# schematic.net
KiCad netlist of a schematic drawn in Altium Designer
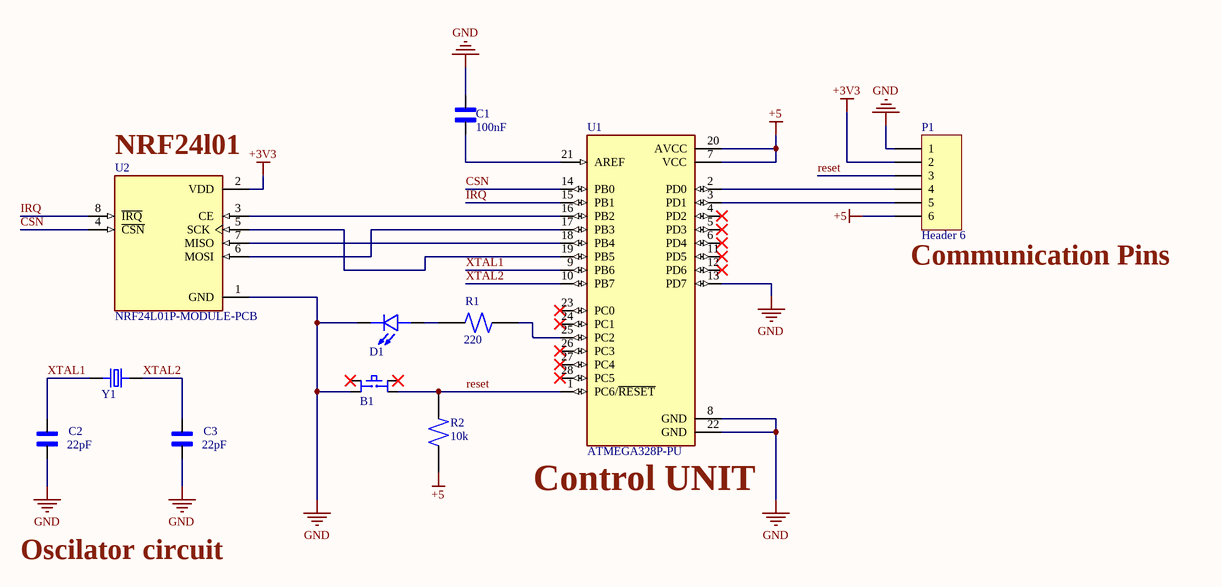
[diagram p0: schematic.SchDoc]

(export (version "E")
  (design (tool "Eeschema 10.0.6"))
  (components
    (comp (ref "B1")
      (value "Push button")
      (footprint "SW_TS02-66-95-BK-260-LCR-D")
      (libsource (lib "Installed library") (part "Push button"))
    )
    (comp (ref "C1")
      (value "100nF")
      (footprint "CAPRB500W50L450T300H550")
      (description "2200 pF Â±10% 250V Ceramic Capacitor X7R Radial")
      (fields (field (name "DIGI-KEY_PART_NUMBER") "445-173386-1-ND") (field (name "MF") "TDK"))
      (libsource (lib "Installed library") (part "Ceramic capacitor"))
    )
    (comp (ref "C2")
      (value "22pF")
      (footprint "CAPRB500W50L450T300H550")
      (description "2200 pF Â±10% 250V Ceramic Capacitor X7R Radial")
      (fields (field (name "DIGI-KEY_PART_NUMBER") "445-173386-1-ND") (field (name "MF") "TDK"))
      (libsource (lib "") (part "Ceramic capacitor_1"))
    )
    (comp (ref "C3")
      (value "22pF")
      (footprint "CAPRB500W50L450T300H550")
      (description "2200 pF Â±10% 250V Ceramic Capacitor X7R Radial")
      (fields (field (name "DIGI-KEY_PART_NUMBER") "445-173386-1-ND") (field (name "MF") "TDK"))
      (libsource (lib "") (part "Ceramic capacitor_1"))
    )
    (comp (ref "D1")
      (value "L08R5000Q1")
      (footprint "LEDRD254W57D500H1070")
      (description "LED, Orange, Through Hole, T-1 3/4 (5mm), 30 mA, 2.1 V, 635 nm")
      (fields (field (name "MF") "{'manufacturer': u'LED Technology'}"))
      (libsource (lib "Installed library") (part "LED"))
    )
    (comp (ref "P1")
      (value "Header 6")
      (footprint "HDR1X6")
      (description "Header, 6-Pin")
      (fields (field (name "PUBLISHER") "Altium Limited"))
      (libsource (lib "Miscellaneous Connectors") (part "Header 6"))
    )
    (comp (ref "R1")
      (value "220")
      (footprint "RESAD1100W55L680D260")
      (description "(MFR-25FBF52-10K) 10,2 kOhm bei 1% 0,25W, 1/4W Durchbohrlochwiderstand Axial Metal Film")
      (fields (field (name "DIGI-KEY_PART_NUMBER") "10.2KXBK-ND") (field (name "MF") "Yageo"))
      (libsource (lib "Installed library") (part "Resistor (0.25W)"))
    )
    (comp (ref "R2")
      (value "10k")
      (footprint "RESAD1100W55L680D260")
      (description "(MFR-25FBF52-10K) 10,2 kOhm bei 1% 0,25W, 1/4W Durchbohrlochwiderstand Axial Metal Film")
      (fields (field (name "DIGI-KEY_PART_NUMBER") "10.2KXBK-ND") (field (name "MF") "Yageo"))
      (libsource (lib "Installed library") (part "Resistor (0.25W)"))
    )
    (comp (ref "U1")
      (value "ATMEGA328P-PU")
      (footprint "DIP794W46P254L2967H457Q28B")
      (description "ATmega Series 20 MHz 32 KB Flash 2 KB SRAM 8-Bit Microcontroller - DIP-28")
      (libsource (lib "Installed library") (part "ATMEGA328P-PU"))
    )
    (comp (ref "U2")
      (value "NRF24L01P-MODULE-PCB")
      (footprint "XCVR_NRF24L01P-MODULE-PCB")
      (description "- Transceiver For Use With nRF24L01+")
      (fields (field (name "MF") "Nordic Semiconductor"))
      (libsource (lib "NRF24L01P-MODULE-PCB") (part "NRF24L01P-MODULE-PCB"))
    )
    (comp (ref "Y1")
      (value "ECS-160-S-4")
      (footprint "XTAL_ECS-160-20-4X")
      (description "CRYSTAL T/H")
      (fields (field (name "MF") "{'manufacturer': u'ECS Inc.'}"))
      (libsource (lib "Installed library") (part "Crystal oscilator"))
    )
  )
  (nets
    (net (code "1") (name "+3V3") (class "Default")
      (node (ref "P1") (pin "2") (pinfunction "2_2") (pintype "passive"))
      (node (ref "U2") (pin "2") (pinfunction "VDD_2") (pintype "power_in"))
    )
    (net (code "2") (name "+5") (class "Default")
      (node (ref "P1") (pin "6") (pinfunction "6_6") (pintype "passive"))
      (node (ref "R2") (pin "1") (pinfunction "1_1") (pintype "passive"))
      (node (ref "U1") (pin "20") (pinfunction "AVCC_20") (pintype "power_in"))
      (node (ref "U1") (pin "7") (pinfunction "VCC_7") (pintype "power_in"))
    )
    (net (code "3") (name "/CSN") (class "Default")
      (node (ref "U1") (pin "14") (pinfunction "PB0_14") (pintype "bidirectional"))
      (node (ref "U2") (pin "4") (pinfunction "~{CSN}_4") (pintype "input"))
    )
    (net (code "4") (name "/IRQ") (class "Default")
      (node (ref "U1") (pin "15") (pinfunction "PB1_15") (pintype "bidirectional"))
      (node (ref "U2") (pin "8") (pinfunction "~{IRQ}_8") (pintype "input"))
    )
    (net (code "5") (name "/XTAL1") (class "Default")
      (node (ref "C2") (pin "2") (pinfunction "2_2") (pintype "passive"))
      (node (ref "U1") (pin "9") (pinfunction "PB6_9") (pintype "bidirectional"))
      (node (ref "Y1") (pin "1") (pinfunction "1_1") (pintype "passive"))
    )
    (net (code "6") (name "/XTAL2") (class "Default")
      (node (ref "C3") (pin "2") (pinfunction "2_2") (pintype "passive"))
      (node (ref "U1") (pin "10") (pinfunction "PB7_10") (pintype "bidirectional"))
      (node (ref "Y1") (pin "2") (pinfunction "2_2") (pintype "passive"))
    )
    (net (code "7") (name "/reset") (class "Default")
      (node (ref "B1") (pin "4") (pinfunction "4_4") (pintype "passive"))
      (node (ref "P1") (pin "3") (pinfunction "3_3") (pintype "passive"))
      (node (ref "R2") (pin "2") (pinfunction "2_2") (pintype "passive"))
      (node (ref "U1") (pin "1") (pinfunction "PC6/~{RESET}_1") (pintype "bidirectional"))
    )
    (net (code "8") (name "GND") (class "Default")
      (node (ref "B1") (pin "2") (pinfunction "2_2") (pintype "passive"))
      (node (ref "C1") (pin "1") (pinfunction "1_1") (pintype "passive"))
      (node (ref "C2") (pin "1") (pinfunction "1_1") (pintype "passive"))
      (node (ref "C3") (pin "1") (pinfunction "1_1") (pintype "passive"))
      (node (ref "D1") (pin "C") (pinfunction "C_C") (pintype "passive"))
      (node (ref "P1") (pin "1") (pinfunction "1_1") (pintype "passive"))
      (node (ref "U1") (pin "13") (pinfunction "PD7_13") (pintype "bidirectional"))
      (node (ref "U1") (pin "22") (pinfunction "GND_22") (pintype "power_in"))
      (node (ref "U1") (pin "8") (pinfunction "GND_8") (pintype "power_in"))
      (node (ref "U2") (pin "1") (pinfunction "GND_1") (pintype "power_in"))
    )
    (net (code "9") (name "Net-(D1-PadA)") (class "Default")
      (node (ref "D1") (pin "A") (pinfunction "A_A") (pintype "passive"))
      (node (ref "R1") (pin "2") (pinfunction "2_2") (pintype "passive"))
    )
    (net (code "10") (name "Net-(U1-AREF)") (class "Default")
      (node (ref "C1") (pin "2") (pinfunction "2_2") (pintype "passive"))
      (node (ref "U1") (pin "21") (pinfunction "AREF_21") (pintype "input"))
    )
    (net (code "11") (name "Net-(U1-PB2)") (class "Default")
      (node (ref "U1") (pin "16") (pinfunction "PB2_16") (pintype "bidirectional"))
      (node (ref "U2") (pin "3") (pinfunction "CE_3") (pintype "input"))
    )
    (net (code "12") (name "Net-(U1-PB3)") (class "Default")
      (node (ref "U1") (pin "17") (pinfunction "PB3_17") (pintype "bidirectional"))
      (node (ref "U2") (pin "6") (pinfunction "MOSI_6") (pintype "input"))
    )
    (net (code "13") (name "Net-(U1-PB4)") (class "Default")
      (node (ref "U1") (pin "18") (pinfunction "PB4_18") (pintype "bidirectional"))
      (node (ref "U2") (pin "7") (pinfunction "MISO_7") (pintype "input"))
    )
    (net (code "14") (name "Net-(U1-PB5)") (class "Default")
      (node (ref "U1") (pin "19") (pinfunction "PB5_19") (pintype "bidirectional"))
      (node (ref "U2") (pin "5") (pinfunction "SCK_5") (pintype "input"))
    )
    (net (code "15") (name "Net-(U1-PC2)") (class "Default")
      (node (ref "R1") (pin "1") (pinfunction "1_1") (pintype "passive"))
      (node (ref "U1") (pin "25") (pinfunction "PC2_25") (pintype "bidirectional"))
    )
    (net (code "16") (name "Net-(U1-PD0)") (class "Default")
      (node (ref "P1") (pin "4") (pinfunction "4_4") (pintype "passive"))
      (node (ref "U1") (pin "2") (pinfunction "PD0_2") (pintype "bidirectional"))
    )
    (net (code "17") (name "Net-(U1-PD1)") (class "Default")
      (node (ref "P1") (pin "5") (pinfunction "5_5") (pintype "passive"))
      (node (ref "U1") (pin "3") (pinfunction "PD1_3") (pintype "bidirectional"))
    )
    (net (code "18") (name "unconnected-(B1-Pad1)") (class "Default")
      (node (ref "B1") (pin "1") (pinfunction "1_1") (pintype "passive+no_connect"))
    )
    (net (code "19") (name "unconnected-(B1-Pad3)") (class "Default")
      (node (ref "B1") (pin "3") (pinfunction "3_3") (pintype "passive+no_connect"))
    )
    (net (code "20") (name "unconnected-(U1-PC0-Pad23)") (class "Default")
      (node (ref "U1") (pin "23") (pinfunction "PC0_23") (pintype "bidirectional+no_connect"))
    )
    (net (code "21") (name "unconnected-(U1-PC1-Pad24)") (class "Default")
      (node (ref "U1") (pin "24") (pinfunction "PC1_24") (pintype "bidirectional+no_connect"))
    )
    (net (code "22") (name "unconnected-(U1-PC3-Pad26)") (class "Default")
      (node (ref "U1") (pin "26") (pinfunction "PC3_26") (pintype "bidirectional+no_connect"))
    )
    (net (code "23") (name "unconnected-(U1-PC4-Pad27)") (class "Default")
      (node (ref "U1") (pin "27") (pinfunction "PC4_27") (pintype "bidirectional+no_connect"))
    )
    (net (code "24") (name "unconnected-(U1-PC5-Pad28)") (class "Default")
      (node (ref "U1") (pin "28") (pinfunction "PC5_28") (pintype "bidirectional+no_connect"))
    )
    (net (code "25") (name "unconnected-(U1-PD2-Pad4)") (class "Default")
      (node (ref "U1") (pin "4") (pinfunction "PD2_4") (pintype "bidirectional+no_connect"))
    )
    (net (code "26") (name "unconnected-(U1-PD3-Pad5)") (class "Default")
      (node (ref "U1") (pin "5") (pinfunction "PD3_5") (pintype "bidirectional+no_connect"))
    )
    (net (code "27") (name "unconnected-(U1-PD4-Pad6)") (class "Default")
      (node (ref "U1") (pin "6") (pinfunction "PD4_6") (pintype "bidirectional+no_connect"))
    )
    (net (code "28") (name "unconnected-(U1-PD5-Pad11)") (class "Default")
      (node (ref "U1") (pin "11") (pinfunction "PD5_11") (pintype "bidirectional+no_connect"))
    )
    (net (code "29") (name "unconnected-(U1-PD6-Pad12)") (class "Default")
      (node (ref "U1") (pin "12") (pinfunction "PD6_12") (pintype "bidirectional+no_connect"))
    )
  )
)
